# EmcoInterfaceBoard_v4.net
KiCad netlist of a schematic drawn in EAGLE
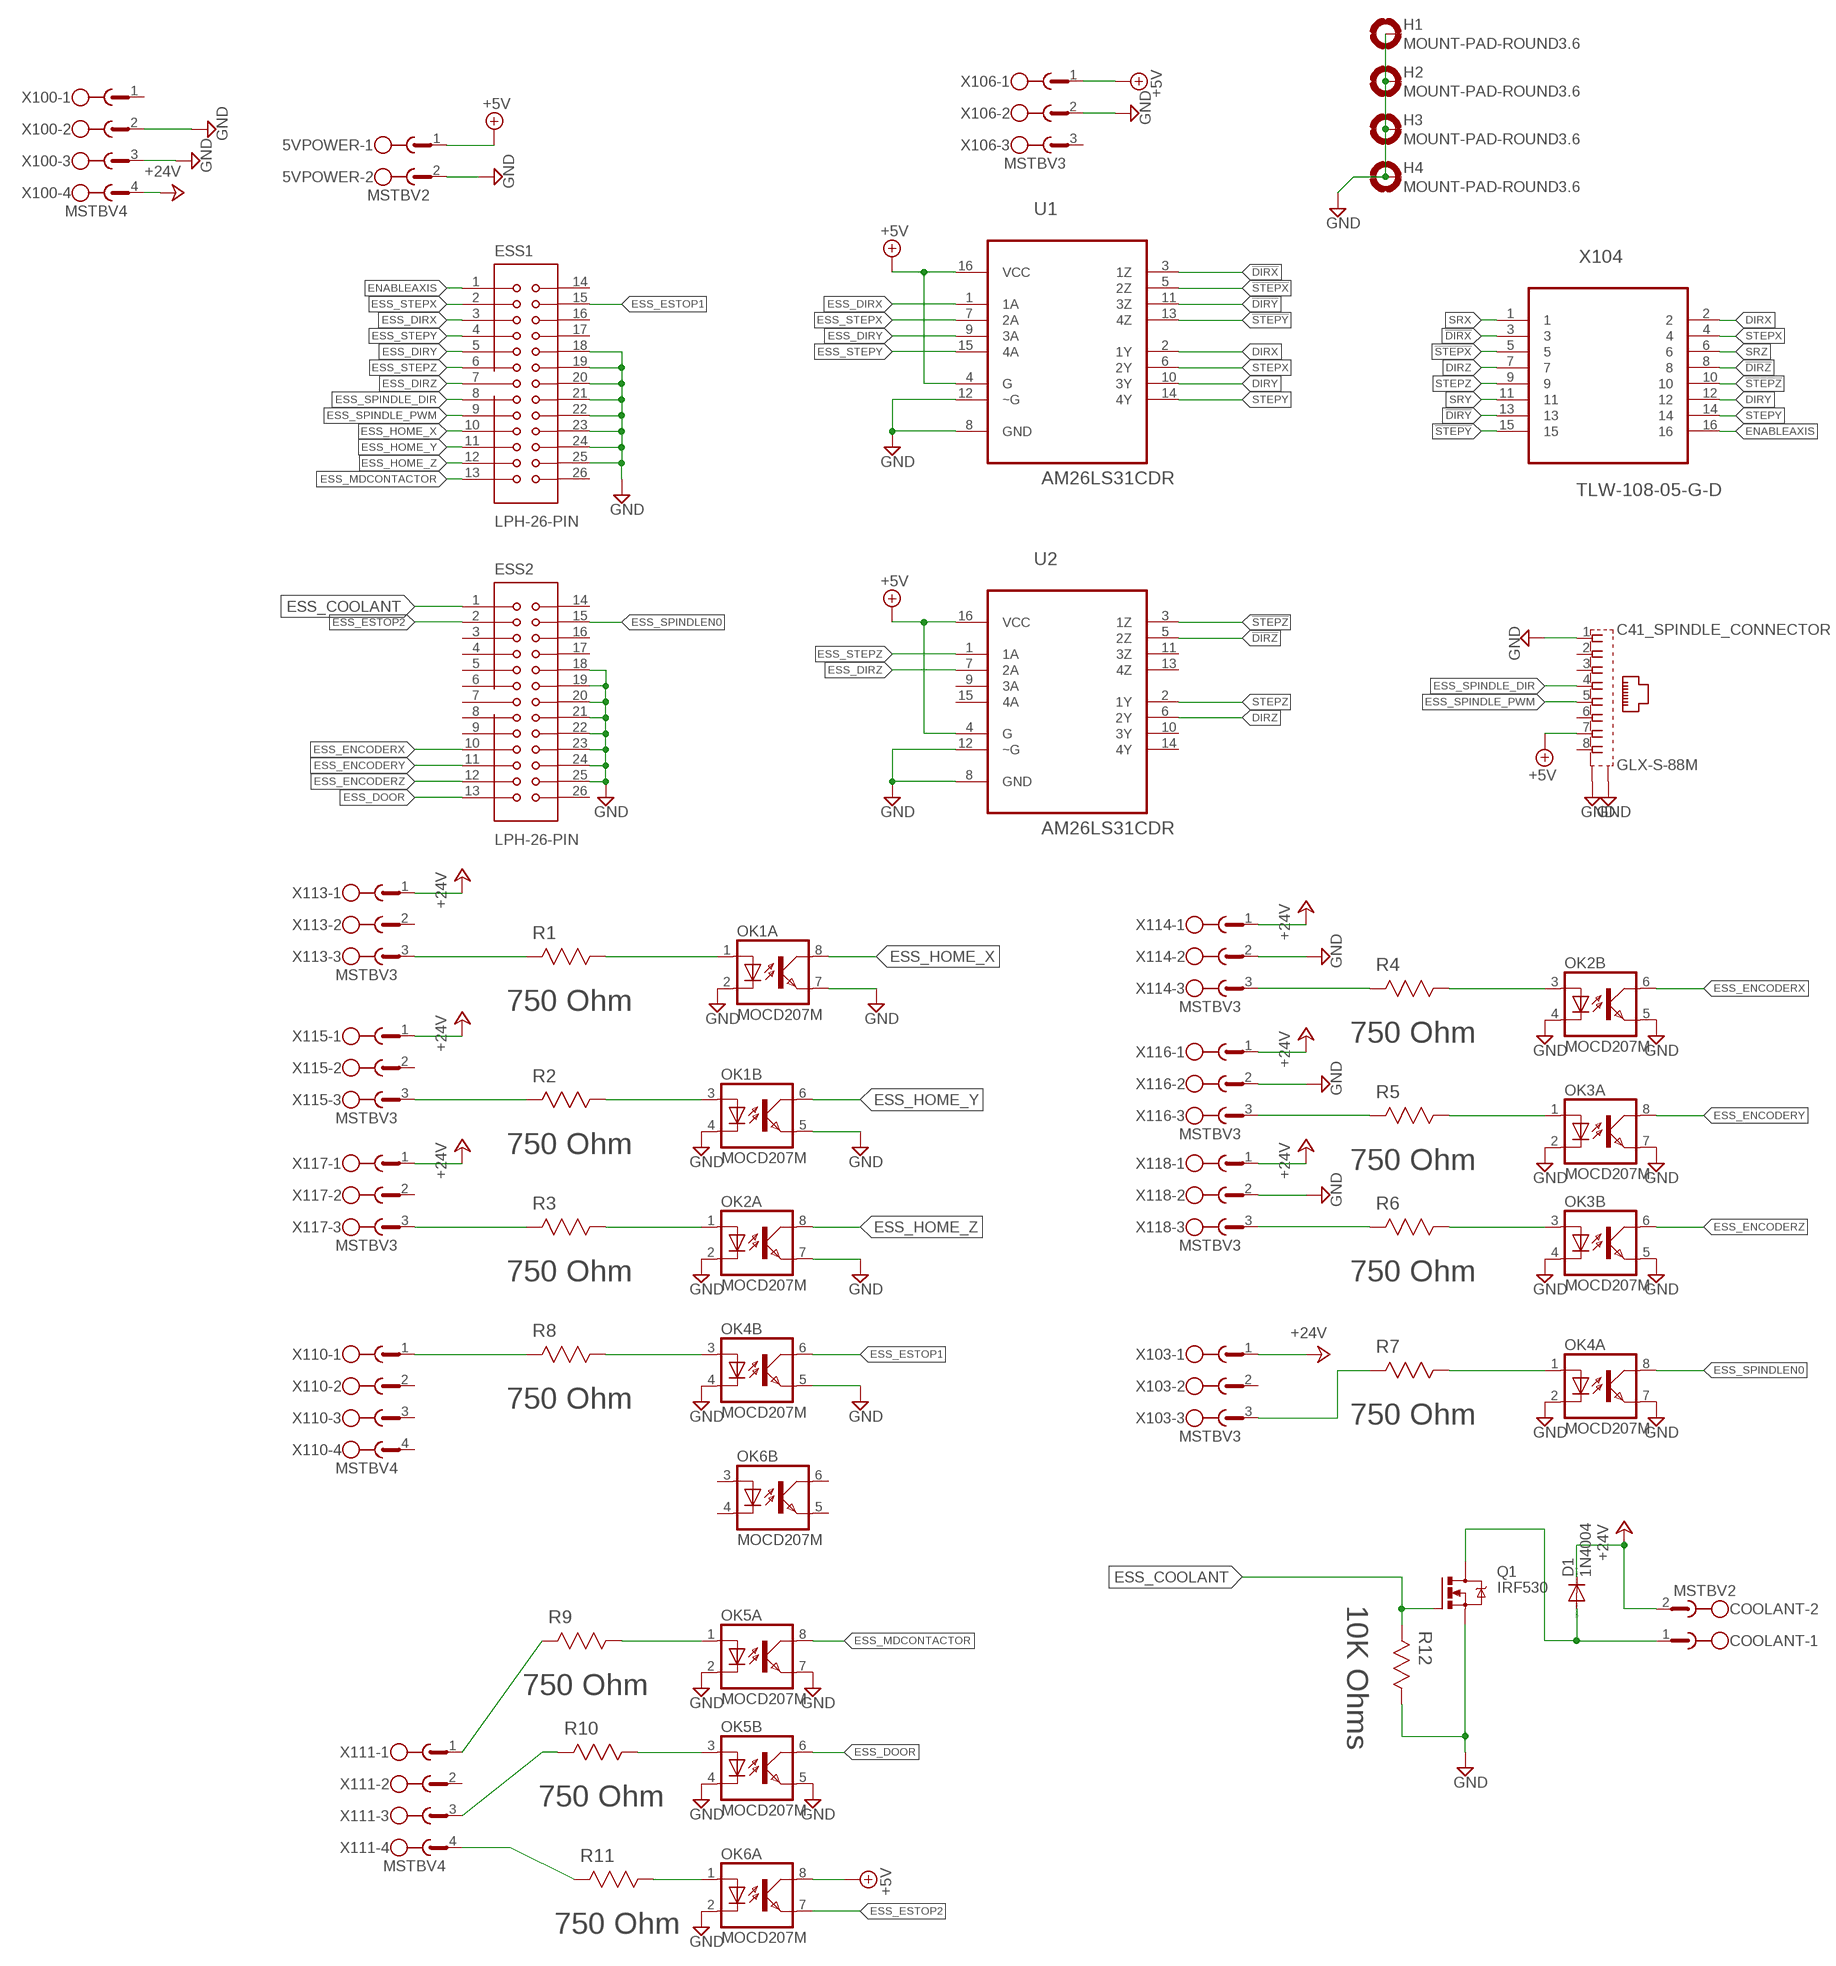
[diagram p0: schematic, sheet 1]

(export (version "E")
  (design (tool "Eeschema 10.0.6"))
  (components
    (comp (ref "5VPOWER")
      (value "MSTBV2")
      (footprint "eagle-import:MSTBV2")
      (fields
        (field (name "MPN") "MSTBV 2,5/2-GF-5.08")
        (field (name "MF") "WEIDMULLER, INC.")
        (field (name "MPN_1") "1521860000")
        (field (name "OC_NEWARK") "36K7716")
      )
      (libsource (lib "eagle-import") (part "MSTBV2"))
    )
    (comp (ref "C41_SPINDLE_CONNECTOR")
      (value "GLX-S-88M")
      (footprint "eagle-import:GLX-S-88M")
      (fields
        (field (name "MF") "MOLEX")
        (field (name "MPN") "43860-0025")
        (field (name "OC_NEWARK") "57H0755")
      )
      (libsource (lib "eagle-import") (part "GLX-S-88M"))
    )
    (comp (ref "COOLANT")
      (value "MSTBV2")
      (footprint "eagle-import:MSTBV2")
      (fields
        (field (name "MPN") "MSTBV 2,5/2-GF-5.08")
        (field (name "MF") "WEIDMULLER, INC.")
        (field (name "MPN_1") "1521860000")
        (field (name "OC_NEWARK") "36K7716")
      )
      (libsource (lib "eagle-import") (part "MSTBV2"))
    )
    (comp (ref "D1")
      (value "1N4004")
      (footprint "eagle-import:DO41-10")
      (fields (field (name "MPN") "1N4007."))
      (libsource (lib "eagle-import") (part "1N4004"))
    )
    (comp (ref "ESS1")
      (value "LPH-26-PIN")
      (footprint "eagle-import:LOWPROFILEHEADER-26PIN")
      (fields (field (name "MF") "TYCO ELECTRONICS") (field (name "MPN") "5103308-6"))
      (libsource (lib "eagle-import") (part "LPH-26-PIN"))
    )
    (comp (ref "ESS2")
      (value "LPH-26-PIN")
      (footprint "eagle-import:LOWPROFILEHEADER-26PIN")
      (fields (field (name "MF") "TYCO ELECTRONICS") (field (name "MPN") "5103308-6"))
      (libsource (lib "eagle-import") (part "LPH-26-PIN"))
    )
    (comp (ref "H1")
      (value "MOUNT-PAD-ROUND3.6")
      (footprint "eagle-import:3,6-PAD")
      (libsource (lib "eagle-import") (part "MOUNT-PAD-ROUND3.6"))
    )
    (comp (ref "H2")
      (value "MOUNT-PAD-ROUND3.6")
      (footprint "eagle-import:3,6-PAD")
      (libsource (lib "eagle-import") (part "MOUNT-PAD-ROUND3.6"))
    )
    (comp (ref "H3")
      (value "MOUNT-PAD-ROUND3.6")
      (footprint "eagle-import:3,6-PAD")
      (libsource (lib "eagle-import") (part "MOUNT-PAD-ROUND3.6"))
    )
    (comp (ref "H4")
      (value "MOUNT-PAD-ROUND3.6")
      (footprint "eagle-import:3,6-PAD")
      (libsource (lib "eagle-import") (part "MOUNT-PAD-ROUND3.6"))
    )
    (comp (ref "OK1")
      (value "MOCD207M")
      (footprint "eagle-import:SOIC08-FAIRCHILD")
      (fields
        (field (name "MF") "FAIRCHILD SEMICONDUCTOR")
        (field (name "MPN") "MOCD207-M")
        (field (name "MPN_1") "MOCD207M")
      )
      (libsource (lib "eagle-import") (part "MOCD20M7"))
    )
    (comp (ref "OK2")
      (value "MOCD207M")
      (footprint "eagle-import:SOIC08-FAIRCHILD")
      (fields
        (field (name "MF") "FAIRCHILD SEMICONDUCTOR")
        (field (name "MPN") "MOCD207-M")
        (field (name "MPN_1") "MOCD207M")
      )
      (libsource (lib "eagle-import") (part "MOCD20M7"))
    )
    (comp (ref "OK3")
      (value "MOCD207M")
      (footprint "eagle-import:SOIC08-FAIRCHILD")
      (fields
        (field (name "MF") "FAIRCHILD SEMICONDUCTOR")
        (field (name "MPN") "MOCD207-M")
        (field (name "MPN_1") "MOCD207M")
      )
      (libsource (lib "eagle-import") (part "MOCD20M7"))
    )
    (comp (ref "OK4")
      (value "MOCD207M")
      (footprint "eagle-import:SOIC08-FAIRCHILD")
      (fields
        (field (name "MF") "FAIRCHILD SEMICONDUCTOR")
        (field (name "MPN") "MOCD207-M")
        (field (name "MPN_1") "MOCD207M")
      )
      (libsource (lib "eagle-import") (part "MOCD20M7"))
    )
    (comp (ref "OK5")
      (value "MOCD207M")
      (footprint "eagle-import:SOIC08-FAIRCHILD")
      (fields
        (field (name "MF") "FAIRCHILD SEMICONDUCTOR")
        (field (name "MPN") "MOCD207-M")
        (field (name "MPN_1") "MOCD207M")
      )
      (libsource (lib "eagle-import") (part "MOCD20M7"))
    )
    (comp (ref "OK6")
      (value "MOCD207M")
      (footprint "eagle-import:SOIC08-FAIRCHILD")
      (fields
        (field (name "MF") "FAIRCHILD SEMICONDUCTOR")
        (field (name "MPN") "MOCD207-M")
        (field (name "MPN_1") "MOCD207M")
      )
      (libsource (lib "eagle-import") (part "MOCD20M7"))
    )
    (comp (ref "Q1")
      (value "IRF530")
      (footprint "eagle-import:TO220BV")
      (fields (field (name "MF") "FAIRCHILD SEMICONDUCTOR") (field (name "MPN") "FQP30N06L"))
      (libsource (lib "eagle-import") (part "IRF530"))
    )
    (comp (ref "R1")
      (value "750 Ohm")
      (footprint "eagle-import:RESC6332X71N")
      (fields
        (field (name "MPN") "CRCW2512750RFKEG")
        (field (name "TOLERANCE") "±1%")
        (field (name "MF") "VISHAY/DALE")
      )
      (libsource (lib "eagle-import") (part "CRCW2512750RFKEG"))
    )
    (comp (ref "R2")
      (value "750 Ohm")
      (footprint "eagle-import:RESC6332X71N")
      (fields
        (field (name "MPN") "CRCW2512750RFKEG")
        (field (name "TOLERANCE") "±1%")
        (field (name "MF") "VISHAY/DALE")
      )
      (libsource (lib "eagle-import") (part "CRCW2512750RFKEG"))
    )
    (comp (ref "R3")
      (value "750 Ohm")
      (footprint "eagle-import:RESC6332X71N")
      (fields
        (field (name "MPN") "CRCW2512750RFKEG")
        (field (name "TOLERANCE") "±1%")
        (field (name "MF") "VISHAY/DALE")
      )
      (libsource (lib "eagle-import") (part "CRCW2512750RFKEG"))
    )
    (comp (ref "R4")
      (value "750 Ohm")
      (footprint "eagle-import:RESC6332X71N")
      (fields
        (field (name "MPN") "CRCW2512750RFKEG")
        (field (name "TOLERANCE") "±1%")
        (field (name "MF") "VISHAY/DALE")
      )
      (libsource (lib "eagle-import") (part "CRCW2512750RFKEG"))
    )
    (comp (ref "R5")
      (value "750 Ohm")
      (footprint "eagle-import:RESC6332X71N")
      (fields
        (field (name "MPN") "CRCW2512750RFKEG")
        (field (name "TOLERANCE") "±1%")
        (field (name "MF") "VISHAY/DALE")
      )
      (libsource (lib "eagle-import") (part "CRCW2512750RFKEG"))
    )
    (comp (ref "R6")
      (value "750 Ohm")
      (footprint "eagle-import:RESC6332X71N")
      (fields
        (field (name "MPN") "CRCW2512750RFKEG")
        (field (name "TOLERANCE") "±1%")
        (field (name "MF") "VISHAY/DALE")
      )
      (libsource (lib "eagle-import") (part "CRCW2512750RFKEG"))
    )
    (comp (ref "R7")
      (value "750 Ohm")
      (footprint "eagle-import:RESC6332X71N")
      (fields
        (field (name "MPN") "CRCW2512750RFKEG")
        (field (name "TOLERANCE") "±1%")
        (field (name "MF") "VISHAY/DALE")
      )
      (libsource (lib "eagle-import") (part "CRCW2512750RFKEG"))
    )
    (comp (ref "R8")
      (value "750 Ohm")
      (footprint "eagle-import:RESC6332X71N")
      (fields
        (field (name "MPN") "CRCW2512750RFKEG")
        (field (name "TOLERANCE") "±1%")
        (field (name "MF") "VISHAY/DALE")
      )
      (libsource (lib "eagle-import") (part "CRCW2512750RFKEG"))
    )
    (comp (ref "R9")
      (value "750 Ohm")
      (footprint "eagle-import:RESC6332X71N")
      (fields
        (field (name "MPN") "CRCW2512750RFKEG")
        (field (name "TOLERANCE") "±1%")
        (field (name "MF") "VISHAY/DALE")
      )
      (libsource (lib "eagle-import") (part "CRCW2512750RFKEG"))
    )
    (comp (ref "R10")
      (value "750 Ohm")
      (footprint "eagle-import:RESC6332X71N")
      (fields
        (field (name "MPN") "CRCW2512750RFKEG")
        (field (name "TOLERANCE") "±1%")
        (field (name "MF") "VISHAY/DALE")
      )
      (libsource (lib "eagle-import") (part "CRCW2512750RFKEG"))
    )
    (comp (ref "R11")
      (value "750 Ohm")
      (footprint "eagle-import:RESC6332X71N")
      (fields
        (field (name "MPN") "CRCW2512750RFKEG")
        (field (name "TOLERANCE") "±1%")
        (field (name "MF") "VISHAY/DALE")
      )
      (libsource (lib "eagle-import") (part "CRCW2512750RFKEG"))
    )
    (comp (ref "R12")
      (value "10K Ohms")
      (footprint "eagle-import:RESC3216X71N")
      (fields
        (field (name "MPN") "MC0.125W12065%10K")
        (field (name "TOLERANCE") "±5%")
        (field (name "MPN_1") "RC1206FR-0710KL")
        (field (name "OC_NEWARK") "68R0292")
      )
      (libsource (lib "eagle-import") (part "MC0.125W12065%10K"))
    )
    (comp (ref "U1")
      (value "AM26LS31CDR")
      (footprint "eagle-import:SOIC127P600X175-16N")
      (fields (field (name "MF") "TEXAS INSTRUMENTS"))
      (libsource (lib "eagle-import") (part "AM26LS31CDR"))
    )
    (comp (ref "U2")
      (value "AM26LS31CDR")
      (footprint "eagle-import:SOIC127P600X175-16N")
      (fields (field (name "MF") "TEXAS INSTRUMENTS"))
      (libsource (lib "eagle-import") (part "AM26LS31CDR"))
    )
    (comp (ref "X100")
      (value "MSTBV4")
      (footprint "eagle-import:MSTBV4")
      (fields
        (field (name "MPN") "MSTBV 2,5/4-GF-5.08")
        (field (name "MF") "WEIDMULLER, INC.")
        (field (name "MPN_1") "1522060000")
        (field (name "OC_NEWARK") "35K5121")
      )
      (libsource (lib "eagle-import") (part "MSTBV4"))
    )
    (comp (ref "X103")
      (value "MSTBV3")
      (footprint "eagle-import:MSTBV3")
      (fields
        (field (name "MPN") "MSTBV 2,5/3-GF-5.08")
        (field (name "MF") "WEIDMULLER, INC.")
        (field (name "MPN_1") "1521960000")
        (field (name "OC_NEWARK") "84F418")
      )
      (libsource (lib "eagle-import") (part "MSTBV3"))
    )
    (comp (ref "X104")
      (value "TLW-108-05-G-D")
      (footprint "eagle-import:SAMTEC_TLW-108-05-G-D")
      (fields
        (field (name "MF") "TYCO ELECTRONICS")
        (field (name "MPN") "2-1761603-6")
        (field (name "OC_NEWARK") "06M6904")
      )
      (libsource (lib "eagle-import") (part "TLW-108-05-G-D"))
    )
    (comp (ref "X106")
      (value "MSTBV3")
      (footprint "eagle-import:MSTBV3")
      (fields
        (field (name "MPN") "MSTBV 2,5/3-GF-5.08")
        (field (name "MF") "WEIDMULLER, INC.")
        (field (name "MPN_1") "1521960000")
        (field (name "OC_NEWARK") "84F418")
      )
      (libsource (lib "eagle-import") (part "MSTBV3"))
    )
    (comp (ref "X110")
      (value "MSTBV4")
      (footprint "eagle-import:MSTBV4")
      (fields
        (field (name "MPN") "MSTBV 2,5/4-GF-5.08")
        (field (name "MF") "WEIDMULLER, INC.")
        (field (name "MPN_1") "1522060000")
        (field (name "OC_NEWARK") "35K5121")
      )
      (libsource (lib "eagle-import") (part "MSTBV4"))
    )
    (comp (ref "X111")
      (value "MSTBV4")
      (footprint "eagle-import:MSTBV4")
      (fields
        (field (name "MPN") "MSTBV 2,5/4-GF-5.08")
        (field (name "MF") "WEIDMULLER, INC.")
        (field (name "MPN_1") "1522060000")
        (field (name "OC_NEWARK") "35K5121")
      )
      (libsource (lib "eagle-import") (part "MSTBV4"))
    )
    (comp (ref "X113")
      (value "MSTBV3")
      (footprint "eagle-import:MSTBV3")
      (fields
        (field (name "MPN") "MSTBV 2,5/3-GF-5.08")
        (field (name "MF") "WEIDMULLER, INC.")
        (field (name "MPN_1") "1521960000")
        (field (name "OC_NEWARK") "84F418")
      )
      (libsource (lib "eagle-import") (part "MSTBV3"))
    )
    (comp (ref "X114")
      (value "MSTBV3")
      (footprint "eagle-import:MSTBV3")
      (fields
        (field (name "MPN") "MSTBV 2,5/3-GF-5.08")
        (field (name "MF") "WEIDMULLER, INC.")
        (field (name "MPN_1") "1521960000")
        (field (name "OC_NEWARK") "84F418")
      )
      (libsource (lib "eagle-import") (part "MSTBV3"))
    )
    (comp (ref "X115")
      (value "MSTBV3")
      (footprint "eagle-import:MSTBV3")
      (fields
        (field (name "MPN") "MSTBV 2,5/3-GF-5.08")
        (field (name "MF") "WEIDMULLER, INC.")
        (field (name "MPN_1") "1521960000")
        (field (name "OC_NEWARK") "84F418")
      )
      (libsource (lib "eagle-import") (part "MSTBV3"))
    )
    (comp (ref "X116")
      (value "MSTBV3")
      (footprint "eagle-import:MSTBV3")
      (fields
        (field (name "MPN") "MSTBV 2,5/3-GF-5.08")
        (field (name "MF") "WEIDMULLER, INC.")
        (field (name "MPN_1") "1521960000")
        (field (name "OC_NEWARK") "84F418")
      )
      (libsource (lib "eagle-import") (part "MSTBV3"))
    )
    (comp (ref "X117")
      (value "MSTBV3")
      (footprint "eagle-import:MSTBV3")
      (fields
        (field (name "MPN") "MSTBV 2,5/3-GF-5.08")
        (field (name "MF") "WEIDMULLER, INC.")
        (field (name "MPN_1") "1521960000")
        (field (name "OC_NEWARK") "84F418")
      )
      (libsource (lib "eagle-import") (part "MSTBV3"))
    )
    (comp (ref "X118")
      (value "MSTBV3")
      (footprint "eagle-import:MSTBV3")
      (fields
        (field (name "MPN") "MSTBV 2,5/3-GF-5.08")
        (field (name "MF") "WEIDMULLER, INC.")
        (field (name "MPN_1") "1521960000")
        (field (name "OC_NEWARK") "84F418")
      )
      (libsource (lib "eagle-import") (part "MSTBV3"))
    )
  )
  (nets
    (net (code "1") (name "+5V") (class "Default")
      (node (ref "5VPOWER") (pin "1") (pinfunction "1_1") (pintype "passive"))
      (node (ref "C41_SPINDLE_CONNECTOR") (pin "7") (pinfunction "7_7") (pintype "passive"))
      (node (ref "OK6") (pin "8") (pinfunction "COL_8") (pintype "passive"))
      (node (ref "U1") (pin "16") (pinfunction "VCC_16") (pintype "power_in"))
      (node (ref "U1") (pin "4") (pinfunction "G_4") (pintype "input"))
      (node (ref "U2") (pin "16") (pinfunction "VCC_16") (pintype "power_in"))
      (node (ref "U2") (pin "4") (pinfunction "G_4") (pintype "input"))
      (node (ref "X106") (pin "1") (pinfunction "1_1") (pintype "passive"))
    )
    (net (code "2") (name "+24V") (class "Default")
      (node (ref "COOLANT") (pin "2") (pinfunction "1_2") (pintype "passive"))
      (node (ref "D1") (pin "C") (pinfunction "C_C") (pintype "passive"))
      (node (ref "X100") (pin "4") (pinfunction "1_4") (pintype "passive"))
      (node (ref "X103") (pin "1") (pinfunction "1_1") (pintype "passive"))
      (node (ref "X113") (pin "1") (pinfunction "1_1") (pintype "passive"))
      (node (ref "X114") (pin "1") (pinfunction "1_1") (pintype "passive"))
      (node (ref "X115") (pin "1") (pinfunction "1_1") (pintype "passive"))
      (node (ref "X116") (pin "1") (pinfunction "1_1") (pintype "passive"))
      (node (ref "X117") (pin "1") (pinfunction "1_1") (pintype "passive"))
      (node (ref "X118") (pin "1") (pinfunction "1_1") (pintype "passive"))
    )
    (net (code "3") (name "/~{DIRX}") (class "Default")
      (node (ref "U1") (pin "3") (pinfunction "1Z_3") (pintype "output"))
      (node (ref "X104") (pin "3") (pinfunction "3_3") (pintype "passive"))
    )
    (net (code "4") (name "/~{DIRY}") (class "Default")
      (node (ref "U1") (pin "11") (pinfunction "3Z_11") (pintype "output"))
      (node (ref "X104") (pin "13") (pinfunction "13_13") (pintype "passive"))
    )
    (net (code "5") (name "/~{DIRZ}") (class "Default")
      (node (ref "U2") (pin "5") (pinfunction "2Z_5") (pintype "output"))
      (node (ref "X104") (pin "8") (pinfunction "8_8") (pintype "passive"))
    )
    (net (code "6") (name "/~{STEPX}") (class "Default")
      (node (ref "U1") (pin "5") (pinfunction "2Z_5") (pintype "output"))
      (node (ref "X104") (pin "5") (pinfunction "5_5") (pintype "passive"))
    )
    (net (code "7") (name "/~{STEPY}") (class "Default")
      (node (ref "U1") (pin "13") (pinfunction "4Z_13") (pintype "output"))
      (node (ref "X104") (pin "15") (pinfunction "15_15") (pintype "passive"))
    )
    (net (code "8") (name "/~{STEPZ}") (class "Default")
      (node (ref "U2") (pin "3") (pinfunction "1Z_3") (pintype "output"))
      (node (ref "X104") (pin "10") (pinfunction "10_10") (pintype "passive"))
    )
    (net (code "9") (name "DIRX") (class "Default")
      (node (ref "U1") (pin "2") (pinfunction "1Y_2") (pintype "output"))
      (node (ref "X104") (pin "2") (pinfunction "2_2") (pintype "passive"))
    )
    (net (code "10") (name "DIRY") (class "Default")
      (node (ref "U1") (pin "10") (pinfunction "3Y_10") (pintype "output"))
      (node (ref "X104") (pin "12") (pinfunction "12_12") (pintype "passive"))
    )
    (net (code "11") (name "DIRZ") (class "Default")
      (node (ref "U2") (pin "6") (pinfunction "2Y_6") (pintype "output"))
      (node (ref "X104") (pin "7") (pinfunction "7_7") (pintype "passive"))
    )
    (net (code "12") (name "ENABLEAXIS") (class "Default")
      (node (ref "ESS1") (pin "1") (pinfunction "P$1_1") (pintype "passive"))
      (node (ref "X104") (pin "16") (pinfunction "16_16") (pintype "passive"))
    )
    (net (code "13") (name "ESS_COOLANT") (class "Default")
      (node (ref "ESS2") (pin "1") (pinfunction "P$1_1") (pintype "passive"))
      (node (ref "Q1") (pin "G") (pinfunction "G_G") (pintype "passive"))
      (node (ref "R12") (pin "2") (pinfunction "R2_2") (pintype "passive"))
    )
    (net (code "14") (name "ESS_DIRX") (class "Default")
      (node (ref "ESS1") (pin "3") (pinfunction "P$3_3") (pintype "passive"))
      (node (ref "U1") (pin "1") (pinfunction "1A_1") (pintype "input"))
    )
    (net (code "15") (name "ESS_DIRY") (class "Default")
      (node (ref "ESS1") (pin "5") (pinfunction "P$5_5") (pintype "passive"))
      (node (ref "U1") (pin "9") (pinfunction "3A_9") (pintype "input"))
    )
    (net (code "16") (name "ESS_DIRZ") (class "Default")
      (node (ref "ESS1") (pin "7") (pinfunction "P$7_7") (pintype "passive"))
      (node (ref "U2") (pin "7") (pinfunction "2A_7") (pintype "input"))
    )
    (net (code "17") (name "ESS_DOOR") (class "Default")
      (node (ref "ESS2") (pin "13") (pinfunction "P$13_13") (pintype "passive"))
      (node (ref "OK5") (pin "6") (pinfunction "COL_6") (pintype "passive"))
    )
    (net (code "18") (name "ESS_ENCODERX") (class "Default")
      (node (ref "ESS2") (pin "10") (pinfunction "P$10_10") (pintype "passive"))
      (node (ref "OK2") (pin "6") (pinfunction "COL_6") (pintype "passive"))
    )
    (net (code "19") (name "ESS_ENCODERY") (class "Default")
      (node (ref "ESS2") (pin "11") (pinfunction "P$11_11") (pintype "passive"))
      (node (ref "OK3") (pin "8") (pinfunction "COL_8") (pintype "passive"))
    )
    (net (code "20") (name "ESS_ENCODERZ") (class "Default")
      (node (ref "ESS2") (pin "12") (pinfunction "P$12_12") (pintype "passive"))
      (node (ref "OK3") (pin "6") (pinfunction "COL_6") (pintype "passive"))
    )
    (net (code "21") (name "ESS_ESTOP1") (class "Default")
      (node (ref "ESS1") (pin "15") (pinfunction "P$15_15") (pintype "passive"))
      (node (ref "OK4") (pin "6") (pinfunction "COL_6") (pintype "passive"))
    )
    (net (code "22") (name "ESS_ESTOP2") (class "Default")
      (node (ref "ESS2") (pin "2") (pinfunction "P$2_2") (pintype "passive"))
      (node (ref "OK6") (pin "7") (pinfunction "EMIT_7") (pintype "passive"))
    )
    (net (code "23") (name "ESS_HOME_X") (class "Default")
      (node (ref "ESS1") (pin "10") (pinfunction "P$10_10") (pintype "passive"))
      (node (ref "OK1") (pin "8") (pinfunction "COL_8") (pintype "passive"))
    )
    (net (code "24") (name "ESS_HOME_Y") (class "Default")
      (node (ref "ESS1") (pin "11") (pinfunction "P$11_11") (pintype "passive"))
      (node (ref "OK1") (pin "6") (pinfunction "COL_6") (pintype "passive"))
    )
    (net (code "25") (name "ESS_HOME_Z") (class "Default")
      (node (ref "ESS1") (pin "12") (pinfunction "P$12_12") (pintype "passive"))
      (node (ref "OK2") (pin "8") (pinfunction "COL_8") (pintype "passive"))
    )
    (net (code "26") (name "ESS_MDCONTACTOR") (class "Default")
      (node (ref "ESS1") (pin "13") (pinfunction "P$13_13") (pintype "passive"))
      (node (ref "OK5") (pin "8") (pinfunction "COL_8") (pintype "passive"))
    )
    (net (code "27") (name "ESS_SPINDLEN0") (class "Default")
      (node (ref "ESS2") (pin "15") (pinfunction "P$15_15") (pintype "passive"))
      (node (ref "OK4") (pin "8") (pinfunction "COL_8") (pintype "passive"))
    )
    (net (code "28") (name "ESS_SPINDLE_DIR") (class "Default")
      (node (ref "C41_SPINDLE_CONNECTOR") (pin "4") (pinfunction "4_4") (pintype "passive"))
      (node (ref "ESS1") (pin "8") (pinfunction "P$8_8") (pintype "passive"))
    )
    (net (code "29") (name "ESS_SPINDLE_PWM") (class "Default")
      (node (ref "C41_SPINDLE_CONNECTOR") (pin "5") (pinfunction "5_5") (pintype "passive"))
      (node (ref "ESS1") (pin "9") (pinfunction "P$9_9") (pintype "passive"))
    )
    (net (code "30") (name "ESS_STEPX") (class "Default")
      (node (ref "ESS1") (pin "2") (pinfunction "P$2_2") (pintype "passive"))
      (node (ref "U1") (pin "7") (pinfunction "2A_7") (pintype "input"))
    )
    (net (code "31") (name "ESS_STEPY") (class "Default")
      (node (ref "ESS1") (pin "4") (pinfunction "P$4_4") (pintype "passive"))
      (node (ref "U1") (pin "15") (pinfunction "4A_15") (pintype "input"))
    )
    (net (code "32") (name "ESS_STEPZ") (class "Default")
      (node (ref "ESS1") (pin "6") (pinfunction "P$6_6") (pintype "passive"))
      (node (ref "U2") (pin "1") (pinfunction "1A_1") (pintype "input"))
    )
    (net (code "33") (name "GND") (class "Default")
      (node (ref "5VPOWER") (pin "2") (pinfunction "1_2") (pintype "passive"))
      (node (ref "C41_SPINDLE_CONNECTOR") (pin "1") (pinfunction "1_1") (pintype "passive"))
      (node (ref "C41_SPINDLE_CONNECTOR") (pin "S1") (pinfunction "S1_S1") (pintype "passive"))
      (node (ref "C41_SPINDLE_CONNECTOR") (pin "S2") (pinfunction "S2_S2") (pintype "passive"))
      (node (ref "ESS1") (pin "18") (pinfunction "P$18_18") (pintype "passive"))
      (node (ref "ESS1") (pin "19") (pinfunction "P$19_19") (pintype "passive"))
      (node (ref "ESS1") (pin "20") (pinfunction "P$20_20") (pintype "passive"))
      (node (ref "ESS1") (pin "21") (pinfunction "P$21_21") (pintype "passive"))
      (node (ref "ESS1") (pin "22") (pinfunction "P$22_22") (pintype "passive"))
      (node (ref "ESS1") (pin "23") (pinfunction "P$23_23") (pintype "passive"))
      (node (ref "ESS1") (pin "24") (pinfunction "P$24_24") (pintype "passive"))
      (node (ref "ESS1") (pin "25") (pinfunction "P$25_25") (pintype "passive"))
      (node (ref "ESS2") (pin "18") (pinfunction "P$18_18") (pintype "passive"))
      (node (ref "ESS2") (pin "19") (pinfunction "P$19_19") (pintype "passive"))
      (node (ref "ESS2") (pin "20") (pinfunction "P$20_20") (pintype "passive"))
      (node (ref "ESS2") (pin "21") (pinfunction "P$21_21") (pintype "passive"))
      (node (ref "ESS2") (pin "22") (pinfunction "P$22_22") (pintype "passive"))
      (node (ref "ESS2") (pin "23") (pinfunction "P$23_23") (pintype "passive"))
      (node (ref "ESS2") (pin "24") (pinfunction "P$24_24") (pintype "passive"))
      (node (ref "ESS2") (pin "25") (pinfunction "P$25_25") (pintype "passive"))
      (node (ref "H1") (pin "B3,6") (pinfunction "MOUNT_B3,6") (pintype "passive"))
      (node (ref "H2") (pin "B3,6") (pinfunction "MOUNT_B3,6") (pintype "passive"))
      (node (ref "H3") (pin "B3,6") (pinfunction "MOUNT_B3,6") (pintype "passive"))
      (node (ref "H4") (pin "B3,6") (pinfunction "MOUNT_B3,6") (pintype "passive"))
      (node (ref "OK1") (pin "2") (pinfunction "C_2") (pintype "passive"))
      (node (ref "OK1") (pin "4") (pinfunction "C_4") (pintype "passive"))
      (node (ref "OK1") (pin "5") (pinfunction "EMIT_5") (pintype "passive"))
      (node (ref "OK1") (pin "7") (pinfunction "EMIT_7") (pintype "passive"))
      (node (ref "OK2") (pin "2") (pinfunction "C_2") (pintype "passive"))
      (node (ref "OK2") (pin "4") (pinfunction "C_4") (pintype "passive"))
      (node (ref "OK2") (pin "5") (pinfunction "EMIT_5") (pintype "passive"))
      (node (ref "OK2") (pin "7") (pinfunction "EMIT_7") (pintype "passive"))
      (node (ref "OK3") (pin "2") (pinfunction "C_2") (pintype "passive"))
      (node (ref "OK3") (pin "4") (pinfunction "C_4") (pintype "passive"))
      (node (ref "OK3") (pin "5") (pinfunction "EMIT_5") (pintype "passive"))
      (node (ref "OK3") (pin "7") (pinfunction "EMIT_7") (pintype "passive"))
      (node (ref "OK4") (pin "2") (pinfunction "C_2") (pintype "passive"))
      (node (ref "OK4") (pin "4") (pinfunction "C_4") (pintype "passive"))
      (node (ref "OK4") (pin "5") (pinfunction "EMIT_5") (pintype "passive"))
      (node (ref "OK4") (pin "7") (pinfunction "EMIT_7") (pintype "passive"))
      (node (ref "OK5") (pin "2") (pinfunction "C_2") (pintype "passive"))
      (node (ref "OK5") (pin "4") (pinfunction "C_4") (pintype "passive"))
      (node (ref "OK5") (pin "5") (pinfunction "EMIT_5") (pintype "passive"))
      (node (ref "OK5") (pin "7") (pinfunction "EMIT_7") (pintype "passive"))
      (node (ref "OK6") (pin "2") (pinfunction "C_2") (pintype "passive"))
      (node (ref "Q1") (pin "S") (pinfunction "S_S") (pintype "passive"))
      (node (ref "R12") (pin "1") (pinfunction "R1_1") (pintype "passive"))
      (node (ref "U1") (pin "12") (pinfunction "~{G}_12") (pintype "input"))
      (node (ref "U1") (pin "8") (pinfunction "GND_8") (pintype "passive"))
      (node (ref "U2") (pin "12") (pinfunction "~{G}_12") (pintype "input"))
      (node (ref "U2") (pin "8") (pinfunction "GND_8") (pintype "passive"))
      (node (ref "X100") (pin "2") (pinfunction "1_2") (pintype "passive"))
      (node (ref "X100") (pin "3") (pinfunction "1_3") (pintype "passive"))
      (node (ref "X106") (pin "2") (pinfunction "1_2") (pintype "passive"))
      (node (ref "X114") (pin "2") (pinfunction "1_2") (pintype "passive"))
      (node (ref "X116") (pin "2") (pinfunction "1_2") (pintype "passive"))
      (node (ref "X118") (pin "2") (pinfunction "1_2") (pintype "passive"))
    )
    (net (code "34") (name "Net-(COOLANT-Pad1)") (class "Default")
      (node (ref "COOLANT") (pin "1") (pinfunction "1_1") (pintype "passive"))
      (node (ref "D1") (pin "A") (pinfunction "A_A") (pintype "passive"))
      (node (ref "Q1") (pin "D") (pinfunction "D_D") (pintype "passive"))
    )
    (net (code "35") (name "Net-(OK1A-A)") (class "Default")
      (node (ref "OK1") (pin "1") (pinfunction "A_1") (pintype "passive"))
      (node (ref "R1") (pin "1") (pinfunction "1_1") (pintype "passive"))
    )
    (net (code "36") (name "Net-(OK1B-A)") (class "Default")
      (node (ref "OK1") (pin "3") (pinfunction "A_3") (pintype "passive"))
      (node (ref "R2") (pin "1") (pinfunction "1_1") (pintype "passive"))
    )
    (net (code "37") (name "Net-(OK2A-A)") (class "Default")
      (node (ref "OK2") (pin "1") (pinfunction "A_1") (pintype "passive"))
      (node (ref "R3") (pin "1") (pinfunction "1_1") (pintype "passive"))
    )
    (net (code "38") (name "Net-(OK2B-A)") (class "Default")
      (node (ref "OK2") (pin "3") (pinfunction "A_3") (pintype "passive"))
      (node (ref "R4") (pin "1") (pinfunction "1_1") (pintype "passive"))
    )
    (net (code "39") (name "Net-(OK3A-A)") (class "Default")
      (node (ref "OK3") (pin "1") (pinfunction "A_1") (pintype "passive"))
      (node (ref "R5") (pin "1") (pinfunction "1_1") (pintype "passive"))
    )
    (net (code "40") (name "Net-(OK3B-A)") (class "Default")
      (node (ref "OK3") (pin "3") (pinfunction "A_3") (pintype "passive"))
      (node (ref "R6") (pin "1") (pinfunction "1_1") (pintype "passive"))
    )
    (net (code "41") (name "Net-(OK4A-A)") (class "Default")
      (node (ref "OK4") (pin "1") (pinfunction "A_1") (pintype "passive"))
      (node (ref "R7") (pin "1") (pinfunction "1_1") (pintype "passive"))
    )
    (net (code "42") (name "Net-(OK4B-A)") (class "Default")
      (node (ref "OK4") (pin "3") (pinfunction "A_3") (pintype "passive"))
      (node (ref "R8") (pin "1") (pinfunction "1_1") (pintype "passive"))
    )
    (net (code "43") (name "Net-(OK5A-A)") (class "Default")
      (node (ref "OK5") (pin "1") (pinfunction "A_1") (pintype "passive"))
      (node (ref "R9") (pin "1") (pinfunction "1_1") (pintype "passive"))
    )
    (net (code "44") (name "Net-(OK5B-A)") (class "Default")
      (node (ref "OK5") (pin "3") (pinfunction "A_3") (pintype "passive"))
      (node (ref "R10") (pin "1") (pinfunction "1_1") (pintype "passive"))
    )
    (net (code "45") (name "Net-(OK6A-A)") (class "Default")
      (node (ref "OK6") (pin "1") (pinfunction "A_1") (pintype "passive"))
      (node (ref "R11") (pin "1") (pinfunction "1_1") (pintype "passive"))
    )
    (net (code "46") (name "Net-(R8-Pad2)") (class "Default")
      (node (ref "R8") (pin "2") (pinfunction "2_2") (pintype "passive"))
      (node (ref "X110") (pin "1") (pinfunction "1_1") (pintype "passive"))
    )
    (net (code "47") (name "Net-(R9-Pad2)") (class "Default")
      (node (ref "R9") (pin "2") (pinfunction "2_2") (pintype "passive"))
      (node (ref "X111") (pin "1") (pinfunction "1_1") (pintype "passive"))
    )
    (net (code "48") (name "Net-(X103C-1)") (class "Default")
      (node (ref "R7") (pin "2") (pinfunction "2_2") (pintype "passive"))
      (node (ref "X103") (pin "3") (pinfunction "1_3") (pintype "passive"))
    )
    (net (code "49") (name "Net-(X111C-1)") (class "Default")
      (node (ref "R10") (pin "2") (pinfunction "2_2") (pintype "passive"))
      (node (ref "X111") (pin "3") (pinfunction "1_3") (pintype "passive"))
    )
    (net (code "50") (name "Net-(X111D-1)") (class "Default")
      (node (ref "R11") (pin "2") (pinfunction "2_2") (pintype "passive"))
      (node (ref "X111") (pin "4") (pinfunction "1_4") (pintype "passive"))
    )
    (net (code "51") (name "Net-(X113C-1)") (class "Default")
      (node (ref "R1") (pin "2") (pinfunction "2_2") (pintype "passive"))
      (node (ref "X113") (pin "3") (pinfunction "1_3") (pintype "passive"))
    )
    (net (code "52") (name "Net-(X114C-1)") (class "Default")
      (node (ref "R4") (pin "2") (pinfunction "2_2") (pintype "passive"))
      (node (ref "X114") (pin "3") (pinfunction "1_3") (pintype "passive"))
    )
    (net (code "53") (name "Net-(X115C-1)") (class "Default")
      (node (ref "R2") (pin "2") (pinfunction "2_2") (pintype "passive"))
      (node (ref "X115") (pin "3") (pinfunction "1_3") (pintype "passive"))
    )
    (net (code "54") (name "Net-(X116C-1)") (class "Default")
      (node (ref "R5") (pin "2") (pinfunction "2_2") (pintype "passive"))
      (node (ref "X116") (pin "3") (pinfunction "1_3") (pintype "passive"))
    )
    (net (code "55") (name "Net-(X117C-1)") (class "Default")
      (node (ref "R3") (pin "2") (pinfunction "2_2") (pintype "passive"))
      (node (ref "X117") (pin "3") (pinfunction "1_3") (pintype "passive"))
    )
    (net (code "56") (name "Net-(X118C-1)") (class "Default")
      (node (ref "R6") (pin "2") (pinfunction "2_2") (pintype "passive"))
      (node (ref "X118") (pin "3") (pinfunction "1_3") (pintype "passive"))
    )
    (net (code "57") (name "SRX") (class "Default")
      (node (ref "X104") (pin "1") (pinfunction "1_1") (pintype "passive"))
    )
    (net (code "58") (name "SRY") (class "Default")
      (node (ref "X104") (pin "11") (pinfunction "11_11") (pintype "passive"))
    )
    (net (code "59") (name "SRZ") (class "Default")
      (node (ref "X104") (pin "6") (pinfunction "6_6") (pintype "passive"))
    )
    (net (code "60") (name "STEPX") (class "Default")
      (node (ref "U1") (pin "6") (pinfunction "2Y_6") (pintype "output"))
      (node (ref "X104") (pin "4") (pinfunction "4_4") (pintype "passive"))
    )
    (net (code "61") (name "STEPY") (class "Default")
      (node (ref "U1") (pin "14") (pinfunction "4Y_14") (pintype "output"))
      (node (ref "X104") (pin "14") (pinfunction "14_14") (pintype "passive"))
    )
    (net (code "62") (name "STEPZ") (class "Default")
      (node (ref "U2") (pin "2") (pinfunction "1Y_2") (pintype "output"))
      (node (ref "X104") (pin "9") (pinfunction "9_9") (pintype "passive"))
    )
    (net (code "63") (name "unconnected-(C41_SPINDLE_CONNECTOR-Pad2)") (class "Default")
      (node (ref "C41_SPINDLE_CONNECTOR") (pin "2") (pinfunction "2_2") (pintype "passive"))
    )
    (net (code "64") (name "unconnected-(C41_SPINDLE_CONNECTOR-Pad3)") (class "Default")
      (node (ref "C41_SPINDLE_CONNECTOR") (pin "3") (pinfunction "3_3") (pintype "passive"))
    )
    (net (code "65") (name "unconnected-(C41_SPINDLE_CONNECTOR-Pad6)") (class "Default")
      (node (ref "C41_SPINDLE_CONNECTOR") (pin "6") (pinfunction "6_6") (pintype "passive"))
    )
    (net (code "66") (name "unconnected-(C41_SPINDLE_CONNECTOR-Pad8)") (class "Default")
      (node (ref "C41_SPINDLE_CONNECTOR") (pin "8") (pinfunction "8_8") (pintype "passive"))
    )
    (net (code "67") (name "unconnected-(ESS1-P$14-Pad14)") (class "Default")
      (node (ref "ESS1") (pin "14") (pinfunction "P$14_14") (pintype "passive"))
    )
    (net (code "68") (name "unconnected-(ESS1-P$16-Pad16)") (class "Default")
      (node (ref "ESS1") (pin "16") (pinfunction "P$16_16") (pintype "passive"))
    )
    (net (code "69") (name "unconnected-(ESS1-P$17-Pad17)") (class "Default")
      (node (ref "ESS1") (pin "17") (pinfunction "P$17_17") (pintype "passive"))
    )
    (net (code "70") (name "unconnected-(ESS1-P$26-Pad26)") (class "Default")
      (node (ref "ESS1") (pin "26") (pinfunction "P$26_26") (pintype "passive"))
    )
    (net (code "71") (name "unconnected-(ESS2-P$3-Pad3)") (class "Default")
      (node (ref "ESS2") (pin "3") (pinfunction "P$3_3") (pintype "passive"))
    )
    (net (code "72") (name "unconnected-(ESS2-P$4-Pad4)") (class "Default")
      (node (ref "ESS2") (pin "4") (pinfunction "P$4_4") (pintype "passive"))
    )
    (net (code "73") (name "unconnected-(ESS2-P$5-Pad5)") (class "Default")
      (node (ref "ESS2") (pin "5") (pinfunction "P$5_5") (pintype "passive"))
    )
    (net (code "74") (name "unconnected-(ESS2-P$6-Pad6)") (class "Default")
      (node (ref "ESS2") (pin "6") (pinfunction "P$6_6") (pintype "passive"))
    )
    (net (code "75") (name "unconnected-(ESS2-P$7-Pad7)") (class "Default")
      (node (ref "ESS2") (pin "7") (pinfunction "P$7_7") (pintype "passive"))
    )
    (net (code "76") (name "unconnected-(ESS2-P$8-Pad8)") (class "Default")
      (node (ref "ESS2") (pin "8") (pinfunction "P$8_8") (pintype "passive"))
    )
    (net (code "77") (name "unconnected-(ESS2-P$9-Pad9)") (class "Default")
      (node (ref "ESS2") (pin "9") (pinfunction "P$9_9") (pintype "passive"))
    )
    (net (code "78") (name "unconnected-(ESS2-P$14-Pad14)") (class "Default")
      (node (ref "ESS2") (pin "14") (pinfunction "P$14_14") (pintype "passive"))
    )
    (net (code "79") (name "unconnected-(ESS2-P$16-Pad16)") (class "Default")
      (node (ref "ESS2") (pin "16") (pinfunction "P$16_16") (pintype "passive"))
    )
    (net (code "80") (name "unconnected-(ESS2-P$17-Pad17)") (class "Default")
      (node (ref "ESS2") (pin "17") (pinfunction "P$17_17") (pintype "passive"))
    )
    (net (code "81") (name "unconnected-(ESS2-P$26-Pad26)") (class "Default")
      (node (ref "ESS2") (pin "26") (pinfunction "P$26_26") (pintype "passive"))
    )
    (net (code "82") (name "unconnected-(OK6B-A-Pad3)") (class "Default")
      (node (ref "OK6") (pin "3") (pinfunction "A_3") (pintype "passive"))
    )
    (net (code "83") (name "unconnected-(OK6B-C-Pad4)") (class "Default")
      (node (ref "OK6") (pin "4") (pinfunction "C_4") (pintype "passive"))
    )
    (net (code "84") (name "unconnected-(OK6B-COL-Pad6)") (class "Default")
      (node (ref "OK6") (pin "6") (pinfunction "COL_6") (pintype "passive"))
    )
    (net (code "85") (name "unconnected-(OK6B-EMIT-Pad5)") (class "Default")
      (node (ref "OK6") (pin "5") (pinfunction "EMIT_5") (pintype "passive"))
    )
    (net (code "86") (name "unconnected-(U2-3A-Pad9)") (class "Default")
      (node (ref "U2") (pin "9") (pinfunction "3A_9") (pintype "input"))
    )
    (net (code "87") (name "unconnected-(U2-3Y-Pad10)") (class "Default")
      (node (ref "U2") (pin "10") (pinfunction "3Y_10") (pintype "output"))
    )
    (net (code "88") (name "unconnected-(U2-3Z-Pad11)") (class "Default")
      (node (ref "U2") (pin "11") (pinfunction "3Z_11") (pintype "output"))
    )
    (net (code "89") (name "unconnected-(U2-4A-Pad15)") (class "Default")
      (node (ref "U2") (pin "15") (pinfunction "4A_15") (pintype "input"))
    )
    (net (code "90") (name "unconnected-(U2-4Y-Pad14)") (class "Default")
      (node (ref "U2") (pin "14") (pinfunction "4Y_14") (pintype "output"))
    )
    (net (code "91") (name "unconnected-(U2-4Z-Pad13)") (class "Default")
      (node (ref "U2") (pin "13") (pinfunction "4Z_13") (pintype "output"))
    )
    (net (code "92") (name "unconnected-(X100-Pad1)") (class "Default")
      (node (ref "X100") (pin "1") (pinfunction "1_1") (pintype "passive"))
    )
    (net (code "93") (name "unconnected-(X103B-1-Pad2)") (class "Default")
      (node (ref "X103") (pin "2") (pinfunction "1_2") (pintype "passive"))
    )
    (net (code "94") (name "unconnected-(X106C-1-Pad3)") (class "Default")
      (node (ref "X106") (pin "3") (pinfunction "1_3") (pintype "passive"))
    )
    (net (code "95") (name "unconnected-(X110B-1-Pad2)") (class "Default")
      (node (ref "X110") (pin "2") (pinfunction "1_2") (pintype "passive"))
    )
    (net (code "96") (name "unconnected-(X110C-1-Pad3)") (class "Default")
      (node (ref "X110") (pin "3") (pinfunction "1_3") (pintype "passive"))
    )
    (net (code "97") (name "unconnected-(X110D-1-Pad4)") (class "Default")
      (node (ref "X110") (pin "4") (pinfunction "1_4") (pintype "passive"))
    )
    (net (code "98") (name "unconnected-(X111B-1-Pad2)") (class "Default")
      (node (ref "X111") (pin "2") (pinfunction "1_2") (pintype "passive"))
    )
    (net (code "99") (name "unconnected-(X113B-1-Pad2)") (class "Default")
      (node (ref "X113") (pin "2") (pinfunction "1_2") (pintype "passive"))
    )
    (net (code "100") (name "unconnected-(X115B-1-Pad2)") (class "Default")
      (node (ref "X115") (pin "2") (pinfunction "1_2") (pintype "passive"))
    )
    (net (code "101") (name "unconnected-(X117B-1-Pad2)") (class "Default")
      (node (ref "X117") (pin "2") (pinfunction "1_2") (pintype "passive"))
    )
  )
)
